# bluetooth.net
KiCad netlist of a schematic drawn in EAGLE
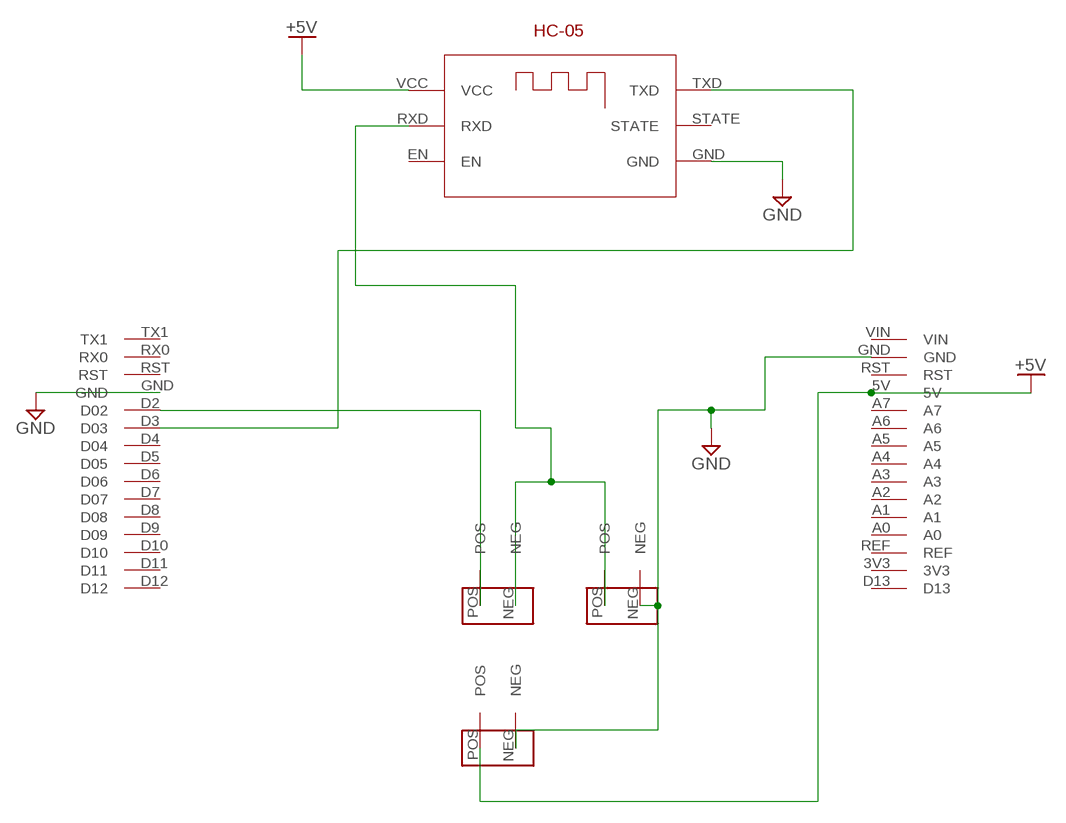
[diagram p0: schematic, sheet 1]

(export (version "E")
  (design (tool "Eeschema 10.0.6"))
  (components
    (comp (ref "POWER")
      (value "CAP")
      (footprint "eagle-import:CAP")
      (libsource (lib "eagle-import") (part "CAP"))
    )
    (comp (ref "U$1")
      (value "ARDUINO-NANO-JUMPER-1")
      (footprint "eagle-import:ARDUINO-NANO-JUMPER-1")
      (libsource (lib "eagle-import") (part "ARDUINO-NANO-JUMPER-1"))
    )
    (comp (ref "U$2")
      (value "ARDUINO-NANO-JUMPER-2")
      (footprint "eagle-import:ARDUINO-NANO-JUMPER-2")
      (libsource (lib "eagle-import") (part "ARDUINO-NANO-JUMPER-2"))
    )
    (comp (ref "U$3")
      (value "RESISTOR")
      (footprint "eagle-import:RESISTOR")
      (libsource (lib "eagle-import") (part "RESISTOR"))
    )
    (comp (ref "U$4")
      (value "RESISTOR")
      (footprint "eagle-import:RESISTOR")
      (libsource (lib "eagle-import") (part "RESISTOR"))
    )
    (comp (ref "U$5")
      (value "HC-05")
      (footprint "eagle-import:HC-05")
      (libsource (lib "eagle-import") (part "HC-05"))
    )
  )
  (nets
    (net (code "1") (name "+5V") (class "Default")
      (node (ref "POWER") (pin "POS") (pinfunction "POS_POS") (pintype "bidirectional"))
      (node (ref "U$2") (pin "5V") (pinfunction "5V_5V") (pintype "bidirectional"))
      (node (ref "U$5") (pin "VCC") (pinfunction "VCC_VCC") (pintype "bidirectional"))
    )
    (net (code "2") (name "GND") (class "Default")
      (node (ref "POWER") (pin "NEG") (pinfunction "NEG_NEG") (pintype "bidirectional"))
      (node (ref "U$1") (pin "GND") (pinfunction "GND_GND") (pintype "bidirectional"))
      (node (ref "U$2") (pin "GND") (pinfunction "GND_GND") (pintype "bidirectional"))
      (node (ref "U$4") (pin "NEG") (pinfunction "NEG_NEG") (pintype "bidirectional"))
      (node (ref "U$5") (pin "GND") (pinfunction "GND_GND") (pintype "bidirectional"))
    )
    (net (code "3") (name "Net-(U$1-D02)") (class "Default")
      (node (ref "U$1") (pin "D2") (pinfunction "D02_D2") (pintype "bidirectional"))
      (node (ref "U$3") (pin "POS") (pinfunction "POS_POS") (pintype "bidirectional"))
    )
    (net (code "4") (name "Net-(U$1-D03)") (class "Default")
      (node (ref "U$1") (pin "D3") (pinfunction "D03_D3") (pintype "bidirectional"))
      (node (ref "U$5") (pin "TXD") (pinfunction "TXD_TXD") (pintype "bidirectional"))
    )
    (net (code "5") (name "Net-(U$3-PadNEG)") (class "Default")
      (node (ref "U$3") (pin "NEG") (pinfunction "NEG_NEG") (pintype "bidirectional"))
      (node (ref "U$4") (pin "POS") (pinfunction "POS_POS") (pintype "bidirectional"))
      (node (ref "U$5") (pin "RXD") (pinfunction "RXD_RXD") (pintype "bidirectional"))
    )
    (net (code "6") (name "unconnected-(U$1-D04-PadD4)") (class "Default")
      (node (ref "U$1") (pin "D4") (pinfunction "D04_D4") (pintype "bidirectional"))
    )
    (net (code "7") (name "unconnected-(U$1-D05-PadD5)") (class "Default")
      (node (ref "U$1") (pin "D5") (pinfunction "D05_D5") (pintype "bidirectional"))
    )
    (net (code "8") (name "unconnected-(U$1-D06-PadD6)") (class "Default")
      (node (ref "U$1") (pin "D6") (pinfunction "D06_D6") (pintype "bidirectional"))
    )
    (net (code "9") (name "unconnected-(U$1-D07-PadD7)") (class "Default")
      (node (ref "U$1") (pin "D7") (pinfunction "D07_D7") (pintype "bidirectional"))
    )
    (net (code "10") (name "unconnected-(U$1-D08-PadD8)") (class "Default")
      (node (ref "U$1") (pin "D8") (pinfunction "D08_D8") (pintype "bidirectional"))
    )
    (net (code "11") (name "unconnected-(U$1-D09-PadD9)") (class "Default")
      (node (ref "U$1") (pin "D9") (pinfunction "D09_D9") (pintype "bidirectional"))
    )
    (net (code "12") (name "unconnected-(U$1-PadD10)") (class "Default")
      (node (ref "U$1") (pin "D10") (pinfunction "D10_D10") (pintype "bidirectional"))
    )
    (net (code "13") (name "unconnected-(U$1-PadD11)") (class "Default")
      (node (ref "U$1") (pin "D11") (pinfunction "D11_D11") (pintype "bidirectional"))
    )
    (net (code "14") (name "unconnected-(U$1-PadD12)") (class "Default")
      (node (ref "U$1") (pin "D12") (pinfunction "D12_D12") (pintype "bidirectional"))
    )
    (net (code "15") (name "unconnected-(U$1-PadRST)") (class "Default")
      (node (ref "U$1") (pin "RST") (pinfunction "RST_RST") (pintype "bidirectional"))
    )
    (net (code "16") (name "unconnected-(U$1-PadRX0)") (class "Default")
      (node (ref "U$1") (pin "RX0") (pinfunction "RX0_RX0") (pintype "bidirectional"))
    )
    (net (code "17") (name "unconnected-(U$1-PadTX1)") (class "Default")
      (node (ref "U$1") (pin "TX1") (pinfunction "TX1_TX1") (pintype "bidirectional"))
    )
    (net (code "18") (name "unconnected-(U$2-Pad3V3)") (class "Default")
      (node (ref "U$2") (pin "3V3") (pinfunction "3V3_3V3") (pintype "bidirectional"))
    )
    (net (code "19") (name "unconnected-(U$2-PadA0)") (class "Default")
      (node (ref "U$2") (pin "A0") (pinfunction "A0_A0") (pintype "bidirectional"))
    )
    (net (code "20") (name "unconnected-(U$2-PadA1)") (class "Default")
      (node (ref "U$2") (pin "A1") (pinfunction "A1_A1") (pintype "bidirectional"))
    )
    (net (code "21") (name "unconnected-(U$2-PadA2)") (class "Default")
      (node (ref "U$2") (pin "A2") (pinfunction "A2_A2") (pintype "bidirectional"))
    )
    (net (code "22") (name "unconnected-(U$2-PadA3)") (class "Default")
      (node (ref "U$2") (pin "A3") (pinfunction "A3_A3") (pintype "bidirectional"))
    )
    (net (code "23") (name "unconnected-(U$2-PadA4)") (class "Default")
      (node (ref "U$2") (pin "A4") (pinfunction "A4_A4") (pintype "bidirectional"))
    )
    (net (code "24") (name "unconnected-(U$2-PadA5)") (class "Default")
      (node (ref "U$2") (pin "A5") (pinfunction "A5_A5") (pintype "bidirectional"))
    )
    (net (code "25") (name "unconnected-(U$2-PadA6)") (class "Default")
      (node (ref "U$2") (pin "A6") (pinfunction "A6_A6") (pintype "bidirectional"))
    )
    (net (code "26") (name "unconnected-(U$2-PadA7)") (class "Default")
      (node (ref "U$2") (pin "A7") (pinfunction "A7_A7") (pintype "bidirectional"))
    )
    (net (code "27") (name "unconnected-(U$2-PadD13)") (class "Default")
      (node (ref "U$2") (pin "D13") (pinfunction "D13_D13") (pintype "bidirectional"))
    )
    (net (code "28") (name "unconnected-(U$2-PadREF)") (class "Default")
      (node (ref "U$2") (pin "REF") (pinfunction "REF_REF") (pintype "bidirectional"))
    )
    (net (code "29") (name "unconnected-(U$2-PadRST)") (class "Default")
      (node (ref "U$2") (pin "RST") (pinfunction "RST_RST") (pintype "bidirectional"))
    )
    (net (code "30") (name "unconnected-(U$2-PadVIN)") (class "Default")
      (node (ref "U$2") (pin "VIN") (pinfunction "VIN_VIN") (pintype "bidirectional"))
    )
    (net (code "31") (name "unconnected-(U$5-PadEN)") (class "Default")
      (node (ref "U$5") (pin "EN") (pinfunction "EN_EN") (pintype "bidirectional"))
    )
    (net (code "32") (name "unconnected-(U$5-PadSTATE)") (class "Default")
      (node (ref "U$5") (pin "STATE") (pinfunction "STATE_STATE") (pintype "bidirectional"))
    )
  )
)
